# LB_BIT_p2_COINBATTERY-v02_rev1.net
KiCad netlist of a schematic drawn in EAGLE
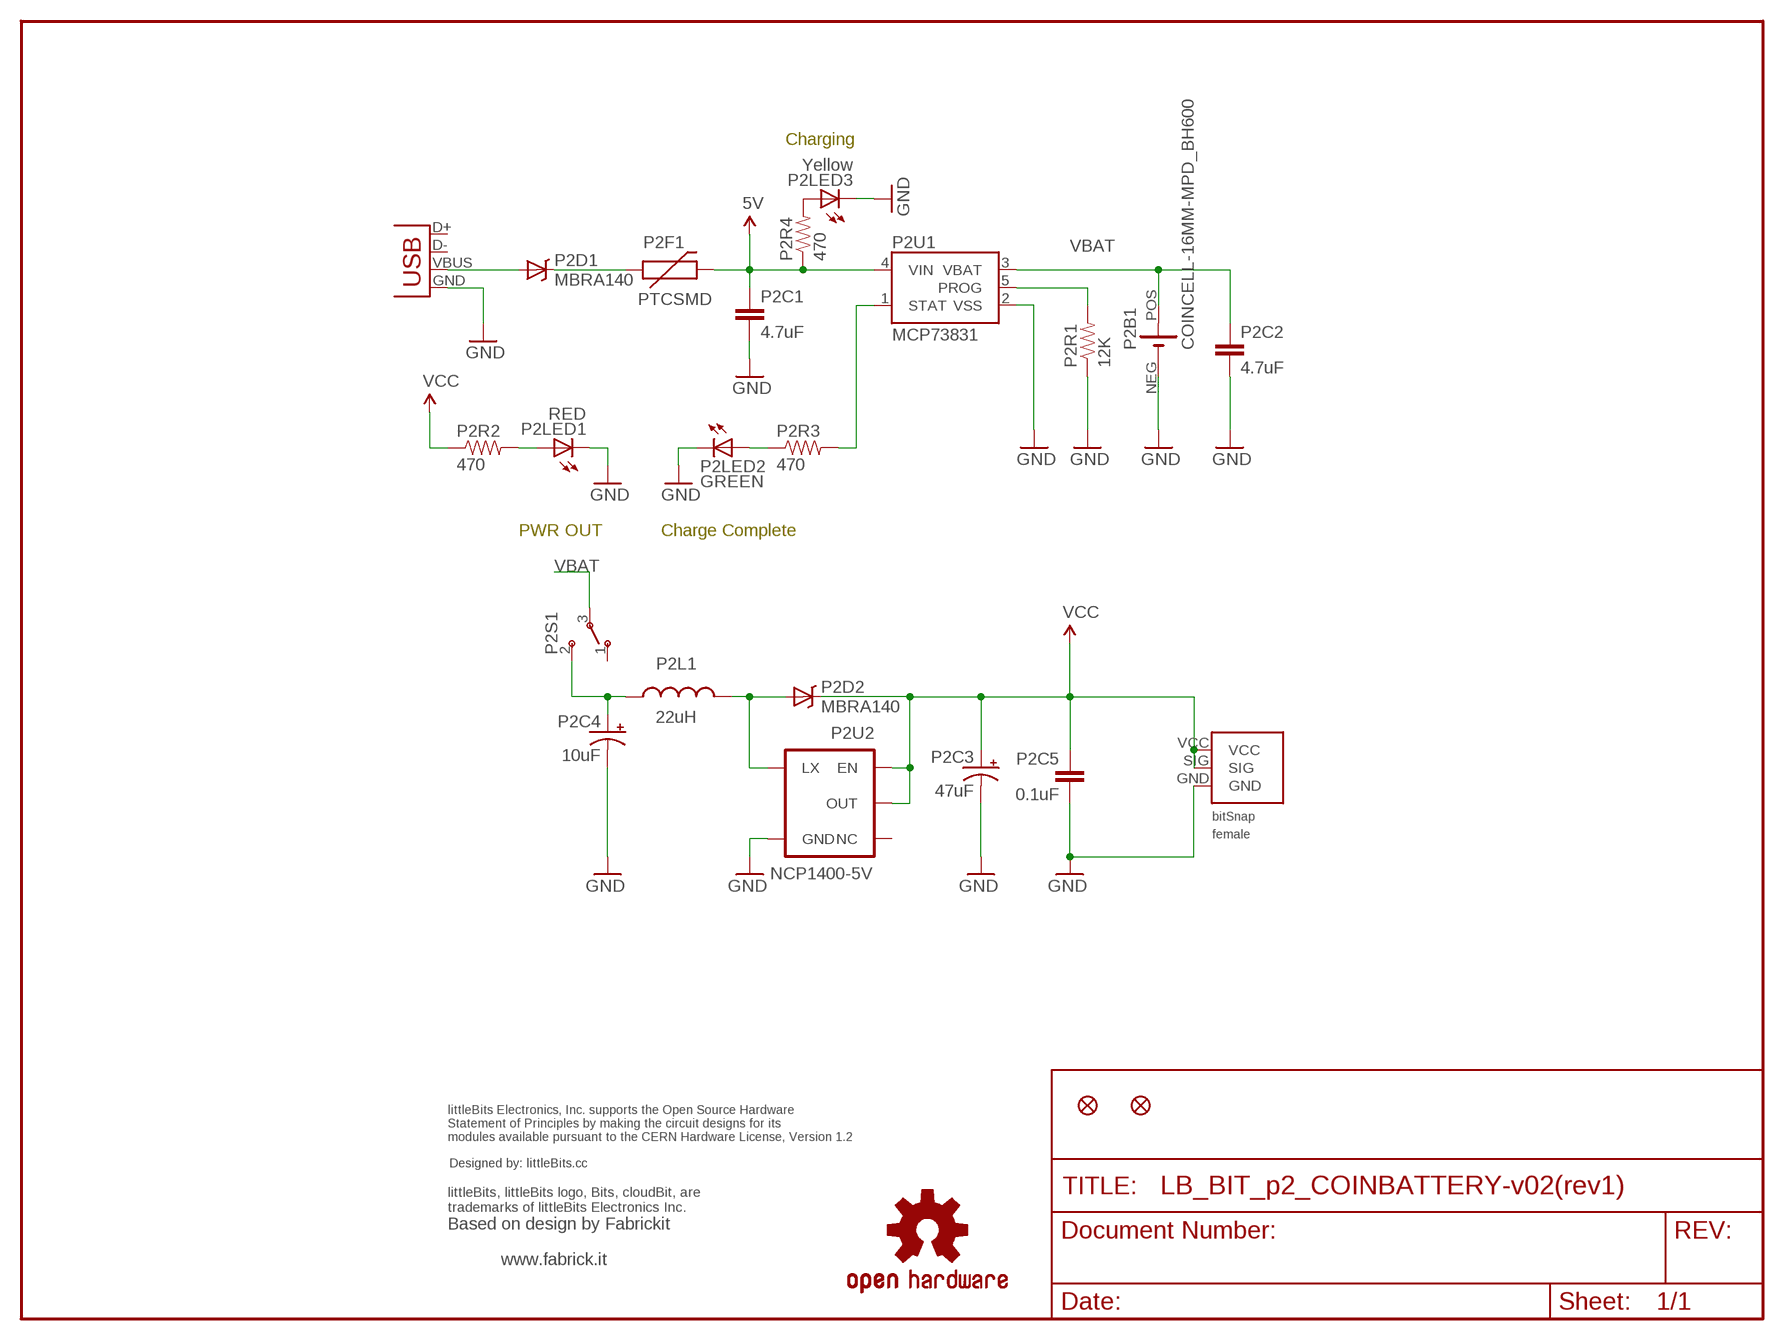
[diagram p0: schematic, sheet 1]

(export (version "E")
  (design (tool "Eeschema 10.0.6"))
  (components
    (comp (ref "JP1")
      (value "FIDUCIAL1X2")
      (footprint "eagle-import:FIDUCIAL-1X2")
      (libsource (lib "eagle-import") (part "FIDUCIAL1X2"))
    )
    (comp (ref "JP2")
      (value "FIDUCIAL1X2")
      (footprint "eagle-import:FIDUCIAL-1X2")
      (libsource (lib "eagle-import") (part "FIDUCIAL1X2"))
    )
    (comp (ref "P2B1")
      (value "COINCELL-16MM-MPD_BH600")
      (footprint "eagle-import:COINCELL-16MM-MPD_BH600")
      (libsource (lib "eagle-import") (part "COINCELL-16MM-MPD_BH600"))
    )
    (comp (ref "P2BSF")
      (value "BITSNAP_FEMALE")
      (footprint "eagle-import:BITSNAP_FEMALE")
      (libsource (lib "eagle-import") (part "BITSNAP_FEMALE"))
    )
    (comp (ref "P2C1")
      (value "4.7uF")
      (footprint "eagle-import:0603-CAP")
      (libsource (lib "eagle-import") (part "CAP0603-CAP"))
    )
    (comp (ref "P2C2")
      (value "4.7uF")
      (footprint "eagle-import:0603-CAP")
      (libsource (lib "eagle-import") (part "CAP0603-CAP"))
    )
    (comp (ref "P2C3")
      (value "47uF")
      (footprint "eagle-import:EIA3528")
      (libsource (lib "eagle-import") (part "CAP_POL3528"))
    )
    (comp (ref "P2C4")
      (value "10uF")
      (footprint "eagle-import:EIA3216")
      (libsource (lib "eagle-import") (part "CAP_POL1206"))
    )
    (comp (ref "P2C5")
      (value "0.1uF")
      (footprint "eagle-import:0603-CAP")
      (libsource (lib "eagle-import") (part "CAP0603-CAP"))
    )
    (comp (ref "P2D1")
      (value "MBRA140")
      (footprint "eagle-import:SMA-DIODE")
      (libsource (lib "eagle-import") (part "DIODE-SCHOTTKY_"))
    )
    (comp (ref "P2D2")
      (value "MBRA140")
      (footprint "eagle-import:SMA-DIODE")
      (libsource (lib "eagle-import") (part "DIODE-SCHOTTKY_"))
    )
    (comp (ref "P2F1")
      (value "PTCSMD")
      (footprint "eagle-import:PTC-1206")
      (libsource (lib "eagle-import") (part "PTCSMD"))
    )
    (comp (ref "P2L1")
      (value "22uH")
      (footprint "eagle-import:INDUCTOR-TAITO_YUDEN_NR6028T220M")
      (libsource (lib "eagle-import") (part "INDUCTOR-TAITO_YUDEN_NR6028T220M"))
    )
    (comp (ref "P2LED1")
      (value "RED")
      (footprint "eagle-import:LED-1206")
      (libsource (lib "eagle-import") (part "LED1206"))
    )
    (comp (ref "P2LED2")
      (value "GREEN")
      (footprint "eagle-import:LED-1206")
      (libsource (lib "eagle-import") (part "LED1206"))
    )
    (comp (ref "P2LED3")
      (value "Yellow")
      (footprint "eagle-import:LED-1206")
      (libsource (lib "eagle-import") (part "LED1206"))
    )
    (comp (ref "P2R1")
      (value "12K")
      (footprint "eagle-import:0603-RES")
      (libsource (lib "eagle-import") (part "RESISTOR0603-RES"))
    )
    (comp (ref "P2R2")
      (value "470")
      (footprint "eagle-import:0603-RES")
      (libsource (lib "eagle-import") (part "RESISTOR0603-RES"))
    )
    (comp (ref "P2R3")
      (value "470")
      (footprint "eagle-import:0603-RES")
      (libsource (lib "eagle-import") (part "RESISTOR0603-RES"))
    )
    (comp (ref "P2R4")
      (value "470")
      (footprint "eagle-import:0603-RES")
      (libsource (lib "eagle-import") (part "RESISTOR0603-RES"))
    )
    (comp (ref "P2S1")
      (value "SWITCH-SMD-SLIDE-CSS1210TB")
      (footprint "eagle-import:COPAL_CSS1210TB")
      (libsource (lib "eagle-import") (part "SWITCH-SMD-SLIDE-CSS1210TB"))
    )
    (comp (ref "P2U1")
      (value "MCP73831")
      (footprint "eagle-import:SOT23-5")
      (libsource (lib "eagle-import") (part "MCP73831"))
    )
    (comp (ref "P2U2")
      (value "NCP1400-5V")
      (footprint "eagle-import:SOT23-5")
      (libsource (lib "eagle-import") (part "V_REG_NCP1400SOT23-5"))
    )
    (comp (ref "P2X1")
      (value "USB-MICROB")
      (footprint "eagle-import:USB-MICROB")
      (libsource (lib "eagle-import") (part "USB-MICROB"))
    )
    (comp (ref "U$3")
      (value "OSHWCREDIT")
      (footprint "eagle-import:OSHWCREDIT")
      (libsource (lib "eagle-import") (part "OSHWCREDIT"))
    )
    (comp (ref "U$4")
      (value "OSHW-LOGOL")
      (footprint "eagle-import:OSHW-LOGO-L")
      (libsource (lib "eagle-import") (part "OSHW-LOGOL"))
    )
  )
  (nets
    (net (code "1") (name "/VBAT") (class "Default")
      (node (ref "P2B1") (pin "POS") (pinfunction "+_POS") (pintype "power_in"))
      (node (ref "P2C2") (pin "1") (pinfunction "1_1") (pintype "passive"))
      (node (ref "P2S1") (pin "3") (pinfunction "3_3") (pintype "passive"))
      (node (ref "P2U1") (pin "3") (pinfunction "VBAT_3") (pintype "power_in"))
    )
    (net (code "2") (name "5V") (class "Default")
      (node (ref "P2C1") (pin "1") (pinfunction "1_1") (pintype "passive"))
      (node (ref "P2F1") (pin "2") (pinfunction "2_2") (pintype "bidirectional"))
      (node (ref "P2R4") (pin "1") (pinfunction "1_1") (pintype "passive"))
      (node (ref "P2U1") (pin "4") (pinfunction "VIN_4") (pintype "power_in"))
    )
    (net (code "3") (name "GND") (class "Default")
      (node (ref "P2B1") (pin "NEG") (pinfunction "-_NEG") (pintype "power_in"))
      (node (ref "P2BSF") (pin "GND") (pinfunction "GND_GND") (pintype "bidirectional"))
      (node (ref "P2C1") (pin "2") (pinfunction "2_2") (pintype "passive"))
      (node (ref "P2C2") (pin "2") (pinfunction "2_2") (pintype "passive"))
      (node (ref "P2C3") (pin "C") (pinfunction "-_C") (pintype "passive"))
      (node (ref "P2C4") (pin "C") (pinfunction "-_C") (pintype "passive"))
      (node (ref "P2C5") (pin "2") (pinfunction "2_2") (pintype "passive"))
      (node (ref "P2LED1") (pin "C") (pinfunction "C_C") (pintype "passive"))
      (node (ref "P2LED2") (pin "C") (pinfunction "C_C") (pintype "passive"))
      (node (ref "P2LED3") (pin "C") (pinfunction "C_C") (pintype "passive"))
      (node (ref "P2R1") (pin "1") (pinfunction "1_1") (pintype "passive"))
      (node (ref "P2U1") (pin "2") (pinfunction "VSS_2") (pintype "power_in"))
      (node (ref "P2U2") (pin "4") (pinfunction "GND_4") (pintype "input"))
      (node (ref "P2X1") (pin "GND") (pinfunction "GND_GND") (pintype "bidirectional"))
    )
    (net (code "4") (name "Net-(P2C4-+)") (class "Default")
      (node (ref "P2C4") (pin "A") (pinfunction "+_A") (pintype "passive"))
      (node (ref "P2L1") (pin "P$2") (pinfunction "2_P$2") (pintype "passive"))
      (node (ref "P2S1") (pin "2") (pinfunction "2_2") (pintype "passive"))
    )
    (net (code "5") (name "Net-(P2D1-PadA)") (class "Default")
      (node (ref "P2D1") (pin "A") (pinfunction "A_A") (pintype "passive"))
      (node (ref "P2X1") (pin "VBUS") (pinfunction "VBUS_VBUS") (pintype "bidirectional"))
    )
    (net (code "6") (name "Net-(P2D1-PadC)") (class "Default")
      (node (ref "P2D1") (pin "C") (pinfunction "C_C") (pintype "passive"))
      (node (ref "P2F1") (pin "1") (pinfunction "1_1") (pintype "bidirectional"))
    )
    (net (code "7") (name "Net-(P2L1-1)") (class "Default")
      (node (ref "P2D2") (pin "A") (pinfunction "A_A") (pintype "passive"))
      (node (ref "P2L1") (pin "P$1") (pinfunction "1_P$1") (pintype "passive"))
      (node (ref "P2U2") (pin "5") (pinfunction "LX_5") (pintype "input"))
    )
    (net (code "8") (name "Net-(P2LED1-PadA)") (class "Default")
      (node (ref "P2LED1") (pin "A") (pinfunction "A_A") (pintype "passive"))
      (node (ref "P2R2") (pin "2") (pinfunction "2_2") (pintype "passive"))
    )
    (net (code "9") (name "Net-(P2LED2-PadA)") (class "Default")
      (node (ref "P2LED2") (pin "A") (pinfunction "A_A") (pintype "passive"))
      (node (ref "P2R3") (pin "1") (pinfunction "1_1") (pintype "passive"))
    )
    (net (code "10") (name "Net-(P2LED3-PadA)") (class "Default")
      (node (ref "P2LED3") (pin "A") (pinfunction "A_A") (pintype "passive"))
      (node (ref "P2R4") (pin "2") (pinfunction "2_2") (pintype "passive"))
    )
    (net (code "11") (name "Net-(P2U1-PROG)") (class "Default")
      (node (ref "P2R1") (pin "2") (pinfunction "2_2") (pintype "passive"))
      (node (ref "P2U1") (pin "5") (pinfunction "PROG_5") (pintype "input"))
    )
    (net (code "12") (name "Net-(P2U1-STAT)") (class "Default")
      (node (ref "P2R3") (pin "2") (pinfunction "2_2") (pintype "passive"))
      (node (ref "P2U1") (pin "1") (pinfunction "STAT_1") (pintype "output"))
    )
    (net (code "13") (name "VCC") (class "Default")
      (node (ref "P2BSF") (pin "SIG") (pinfunction "SIG_SIG") (pintype "bidirectional"))
      (node (ref "P2BSF") (pin "VCC") (pinfunction "VCC_VCC") (pintype "bidirectional"))
      (node (ref "P2C3") (pin "A") (pinfunction "+_A") (pintype "passive"))
      (node (ref "P2C5") (pin "1") (pinfunction "1_1") (pintype "passive"))
      (node (ref "P2D2") (pin "C") (pinfunction "C_C") (pintype "passive"))
      (node (ref "P2R2") (pin "1") (pinfunction "1_1") (pintype "passive"))
      (node (ref "P2U2") (pin "1") (pinfunction "EN_1") (pintype "input"))
      (node (ref "P2U2") (pin "2") (pinfunction "OUT_2") (pintype "passive"))
    )
    (net (code "14") (name "unconnected-(P2S1-Pad1)") (class "Default")
      (node (ref "P2S1") (pin "1") (pinfunction "1_1") (pintype "passive"))
    )
    (net (code "15") (name "unconnected-(P2U2-NC-Pad3)") (class "Default")
      (node (ref "P2U2") (pin "3") (pinfunction "NC_3") (pintype "input"))
    )
    (net (code "16") (name "unconnected-(P2X1-PadD+)") (class "Default")
      (node (ref "P2X1") (pin "D+") (pinfunction "D+_D+") (pintype "bidirectional"))
    )
    (net (code "17") (name "unconnected-(P2X1-PadD-)") (class "Default")
      (node (ref "P2X1") (pin "D-") (pinfunction "D-_D-") (pintype "bidirectional"))
    )
  )
)
